# newday_alt_v0001.net
KiCad netlist of a schematic drawn in EAGLE
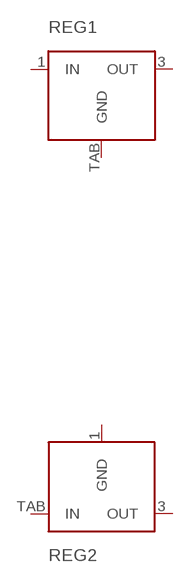
[diagram p0: schematic, sheet 1]
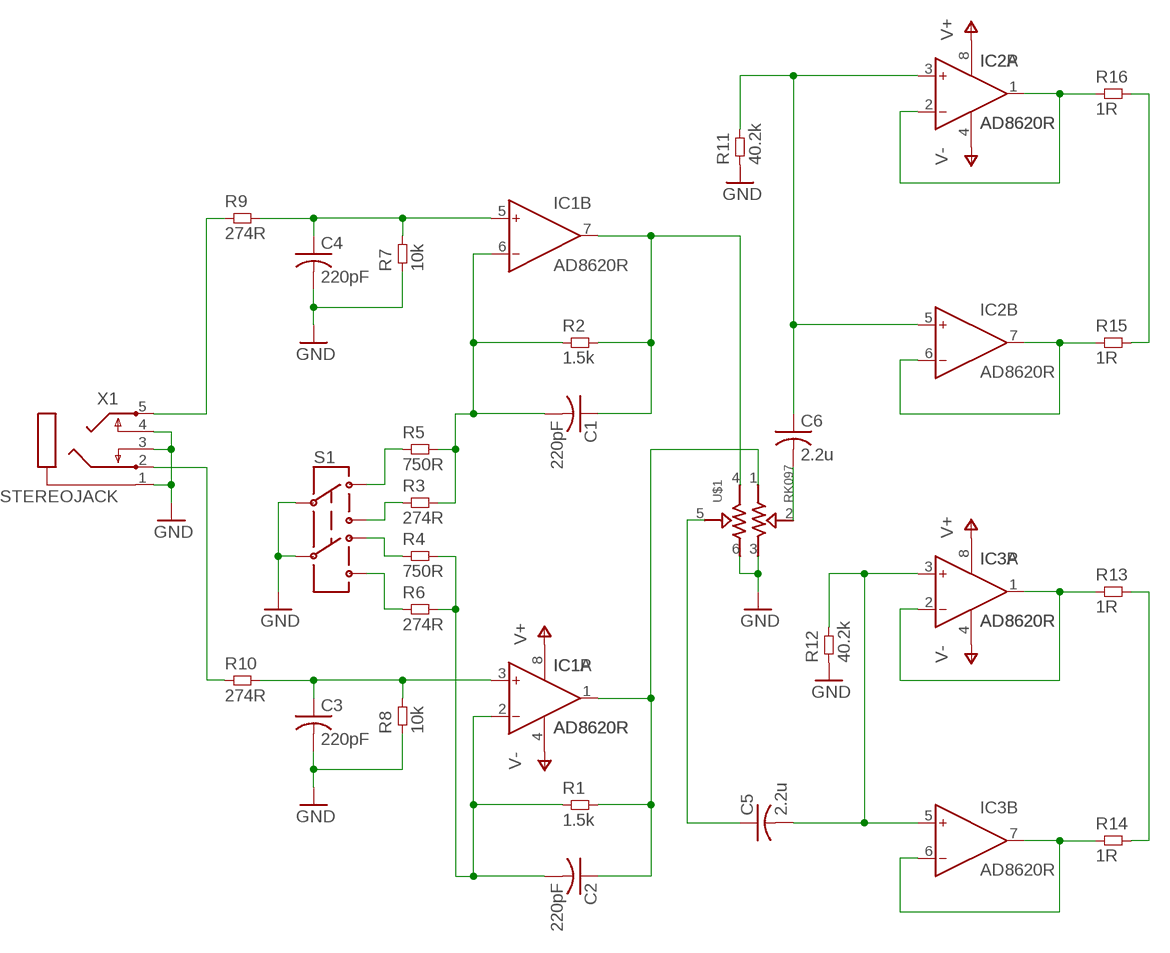
[diagram p1: schematic, sheet 2]

(export (version "E")
  (design (tool "Eeschema 10.0.6"))
  (components
    (comp (ref "REG1")
      (value "MC7812")
      (footprint "eagle-import:D2PAK")
      (libsource (lib "eagle-import") (part "MC7812"))
    )
    (comp (ref "REG2")
      (value "MC7912")
      (footprint "eagle-import:D2PAK")
      (libsource (lib "eagle-import") (part "MC7912"))
    )
    (comp (ref "C1")
      (value "220pF")
      (footprint "eagle-import:C025-040X050")
      (libsource (lib "eagle-import") (part "C-US025-040X050"))
    )
    (comp (ref "C2")
      (value "220pF")
      (footprint "eagle-import:C025-040X050")
      (libsource (lib "eagle-import") (part "C-US025-040X050"))
    )
    (comp (ref "C3")
      (value "220pF")
      (footprint "eagle-import:C025-040X050")
      (libsource (lib "eagle-import") (part "C-US025-040X050"))
    )
    (comp (ref "C4")
      (value "220pF")
      (footprint "eagle-import:C025-040X050")
      (libsource (lib "eagle-import") (part "C-US025-040X050"))
    )
    (comp (ref "C5")
      (value "2.2u")
      (footprint "eagle-import:C050-075X075")
      (libsource (lib "eagle-import") (part "C-US050-075X075"))
    )
    (comp (ref "C6")
      (value "2.2u")
      (footprint "eagle-import:C050-075X075")
      (libsource (lib "eagle-import") (part "C-US050-075X075"))
    )
    (comp (ref "IC1")
      (value "AD8620R")
      (footprint "eagle-import:SO8")
      (fields (field (name "MF") "ALTERA CORPORATION") (field (name "MPN") "AD8620ARZ"))
      (libsource (lib "eagle-import") (part "AD8620R"))
    )
    (comp (ref "IC2")
      (value "AD8620R")
      (footprint "eagle-import:SO8")
      (fields (field (name "MF") "ALTERA CORPORATION") (field (name "MPN") "AD8620ARZ"))
      (libsource (lib "eagle-import") (part "AD8620R"))
    )
    (comp (ref "IC3")
      (value "AD8620R")
      (footprint "eagle-import:SO8")
      (fields (field (name "MF") "ALTERA CORPORATION") (field (name "MPN") "AD8620ARZ"))
      (libsource (lib "eagle-import") (part "AD8620R"))
    )
    (comp (ref "R1")
      (value "1.5k")
      (footprint "eagle-import:0603L3")
      (libsource (lib "eagle-import") (part "RES0603L3"))
    )
    (comp (ref "R2")
      (value "1.5k")
      (footprint "eagle-import:0603L3")
      (libsource (lib "eagle-import") (part "RES0603L3"))
    )
    (comp (ref "R3")
      (value "274R")
      (footprint "eagle-import:0603L3")
      (libsource (lib "eagle-import") (part "RES0603L3"))
    )
    (comp (ref "R4")
      (value "750R")
      (footprint "eagle-import:0603L3")
      (libsource (lib "eagle-import") (part "RES0603L3"))
    )
    (comp (ref "R5")
      (value "750R")
      (footprint "eagle-import:0603L3")
      (libsource (lib "eagle-import") (part "RES0603L3"))
    )
    (comp (ref "R6")
      (value "274R")
      (footprint "eagle-import:0603L3")
      (libsource (lib "eagle-import") (part "RES0603L3"))
    )
    (comp (ref "R7")
      (value "10k")
      (footprint "eagle-import:0603L3")
      (libsource (lib "eagle-import") (part "RES0603L3"))
    )
    (comp (ref "R8")
      (value "10k")
      (footprint "eagle-import:0603L3")
      (libsource (lib "eagle-import") (part "RES0603L3"))
    )
    (comp (ref "R9")
      (value "274R")
      (footprint "eagle-import:0603L3")
      (libsource (lib "eagle-import") (part "RES0603L3"))
    )
    (comp (ref "R10")
      (value "274R")
      (footprint "eagle-import:0603L3")
      (libsource (lib "eagle-import") (part "RES0603L3"))
    )
    (comp (ref "R11")
      (value "40.2k")
      (footprint "eagle-import:0603L3")
      (libsource (lib "eagle-import") (part "RES0603L3"))
    )
    (comp (ref "R12")
      (value "40.2k")
      (footprint "eagle-import:0603L3")
      (libsource (lib "eagle-import") (part "RES0603L3"))
    )
    (comp (ref "R13")
      (value "1R")
      (footprint "eagle-import:1210L3")
      (libsource (lib "eagle-import") (part "RES1210L3"))
    )
    (comp (ref "R14")
      (value "1R")
      (footprint "eagle-import:1210L3")
      (libsource (lib "eagle-import") (part "RES1210L3"))
    )
    (comp (ref "R15")
      (value "1R")
      (footprint "eagle-import:1210L3")
      (libsource (lib "eagle-import") (part "RES1210L3"))
    )
    (comp (ref "R16")
      (value "1R")
      (footprint "eagle-import:1210L3")
      (libsource (lib "eagle-import") (part "RES1210L3"))
    )
    (comp (ref "S1")
      (value "SWITCH-DPDTOS")
      (footprint "eagle-import:OS")
      (libsource (lib "eagle-import") (part "SWITCH-DPDTOS"))
    )
    (comp (ref "U$1")
      (value "RK097")
      (footprint "eagle-import:RK097")
      (libsource (lib "eagle-import") (part "RK097"))
    )
    (comp (ref "X1")
      (value "STEREOJACK")
      (footprint "eagle-import:STX3100")
      (libsource (lib "eagle-import") (part "STEREOJACK"))
    )
  )
  (nets
    (net (code "1") (name "GND") (class "Default")
      (node (ref "C3") (pin "2") (pinfunction "2_2") (pintype "passive"))
      (node (ref "C4") (pin "2") (pinfunction "2_2") (pintype "passive"))
      (node (ref "R11") (pin "P$1") (pinfunction "1_P$1") (pintype "bidirectional"))
      (node (ref "R12") (pin "P$1") (pinfunction "1_P$1") (pintype "bidirectional"))
      (node (ref "R7") (pin "P$1") (pinfunction "1_P$1") (pintype "bidirectional"))
      (node (ref "R8") (pin "P$1") (pinfunction "1_P$1") (pintype "bidirectional"))
      (node (ref "S1") (pin "2") (pinfunction "2_2") (pintype "bidirectional"))
      (node (ref "S1") (pin "5") (pinfunction "5_5") (pintype "bidirectional"))
      (node (ref "U$1") (pin "3") (pinfunction "3_3") (pintype "bidirectional"))
      (node (ref "U$1") (pin "6") (pinfunction "6_6") (pintype "bidirectional"))
      (node (ref "X1") (pin "1") (pinfunction "1_1") (pintype "passive"))
      (node (ref "X1") (pin "3") (pinfunction "3_3") (pintype "passive"))
      (node (ref "X1") (pin "4") (pinfunction "4_4") (pintype "passive"))
    )
    (net (code "2") (name "Net-(C5-Pad1)") (class "Default")
      (node (ref "C5") (pin "1") (pinfunction "1_1") (pintype "passive"))
      (node (ref "U$1") (pin "5") (pinfunction "5_5") (pintype "bidirectional"))
    )
    (net (code "3") (name "Net-(C6-Pad2)") (class "Default")
      (node (ref "C6") (pin "2") (pinfunction "2_2") (pintype "passive"))
      (node (ref "U$1") (pin "2") (pinfunction "2_2") (pintype "bidirectional"))
    )
    (net (code "4") (name "Net-(IC1A-IN+)") (class "Default")
      (node (ref "C3") (pin "1") (pinfunction "1_1") (pintype "passive"))
      (node (ref "IC1") (pin "3") (pinfunction "IN+_3") (pintype "input"))
      (node (ref "R10") (pin "P$2") (pinfunction "2_P$2") (pintype "bidirectional"))
      (node (ref "R8") (pin "P$2") (pinfunction "2_P$2") (pintype "bidirectional"))
    )
    (net (code "5") (name "Net-(IC1A-IN-)") (class "Default")
      (node (ref "C2") (pin "2") (pinfunction "2_2") (pintype "passive"))
      (node (ref "IC1") (pin "2") (pinfunction "IN-_2") (pintype "input"))
      (node (ref "R1") (pin "P$1") (pinfunction "1_P$1") (pintype "bidirectional"))
      (node (ref "R4") (pin "P$2") (pinfunction "2_P$2") (pintype "bidirectional"))
      (node (ref "R6") (pin "P$2") (pinfunction "2_P$2") (pintype "bidirectional"))
    )
    (net (code "6") (name "Net-(IC1A-OUT)") (class "Default")
      (node (ref "C2") (pin "1") (pinfunction "1_1") (pintype "passive"))
      (node (ref "IC1") (pin "1") (pinfunction "OUT_1") (pintype "output"))
      (node (ref "R1") (pin "P$2") (pinfunction "2_P$2") (pintype "bidirectional"))
      (node (ref "U$1") (pin "1") (pinfunction "1_1") (pintype "bidirectional"))
    )
    (net (code "7") (name "Net-(IC1B-IN+)") (class "Default")
      (node (ref "C4") (pin "1") (pinfunction "1_1") (pintype "passive"))
      (node (ref "IC1") (pin "5") (pinfunction "IN+_5") (pintype "input"))
      (node (ref "R7") (pin "P$2") (pinfunction "2_P$2") (pintype "bidirectional"))
      (node (ref "R9") (pin "P$2") (pinfunction "2_P$2") (pintype "bidirectional"))
    )
    (net (code "8") (name "Net-(IC1B-IN-)") (class "Default")
      (node (ref "C1") (pin "2") (pinfunction "2_2") (pintype "passive"))
      (node (ref "IC1") (pin "6") (pinfunction "IN-_6") (pintype "input"))
      (node (ref "R2") (pin "P$1") (pinfunction "1_P$1") (pintype "bidirectional"))
      (node (ref "R3") (pin "P$2") (pinfunction "2_P$2") (pintype "bidirectional"))
      (node (ref "R5") (pin "P$2") (pinfunction "2_P$2") (pintype "bidirectional"))
    )
    (net (code "9") (name "Net-(IC1B-OUT)") (class "Default")
      (node (ref "C1") (pin "1") (pinfunction "1_1") (pintype "passive"))
      (node (ref "IC1") (pin "7") (pinfunction "OUT_7") (pintype "output"))
      (node (ref "R2") (pin "P$2") (pinfunction "2_P$2") (pintype "bidirectional"))
      (node (ref "U$1") (pin "4") (pinfunction "4_4") (pintype "bidirectional"))
    )
    (net (code "10") (name "Net-(IC2A-IN+)") (class "Default")
      (node (ref "C6") (pin "1") (pinfunction "1_1") (pintype "passive"))
      (node (ref "IC2") (pin "3") (pinfunction "IN+_3") (pintype "input"))
      (node (ref "IC2") (pin "5") (pinfunction "IN+_5") (pintype "input"))
      (node (ref "R11") (pin "P$2") (pinfunction "2_P$2") (pintype "bidirectional"))
    )
    (net (code "11") (name "Net-(IC2A-IN-)") (class "Default")
      (node (ref "IC2") (pin "1") (pinfunction "OUT_1") (pintype "output"))
      (node (ref "IC2") (pin "2") (pinfunction "IN-_2") (pintype "input"))
      (node (ref "R16") (pin "P$1") (pinfunction "1_P$1") (pintype "bidirectional"))
    )
    (net (code "12") (name "Net-(IC2B-IN-)") (class "Default")
      (node (ref "IC2") (pin "6") (pinfunction "IN-_6") (pintype "input"))
      (node (ref "IC2") (pin "7") (pinfunction "OUT_7") (pintype "output"))
      (node (ref "R15") (pin "P$1") (pinfunction "1_P$1") (pintype "bidirectional"))
    )
    (net (code "13") (name "Net-(IC3A-IN+)") (class "Default")
      (node (ref "C5") (pin "2") (pinfunction "2_2") (pintype "passive"))
      (node (ref "IC3") (pin "3") (pinfunction "IN+_3") (pintype "input"))
      (node (ref "IC3") (pin "5") (pinfunction "IN+_5") (pintype "input"))
      (node (ref "R12") (pin "P$2") (pinfunction "2_P$2") (pintype "bidirectional"))
    )
    (net (code "14") (name "Net-(IC3A-IN-)") (class "Default")
      (node (ref "IC3") (pin "1") (pinfunction "OUT_1") (pintype "output"))
      (node (ref "IC3") (pin "2") (pinfunction "IN-_2") (pintype "input"))
      (node (ref "R13") (pin "P$1") (pinfunction "1_P$1") (pintype "bidirectional"))
    )
    (net (code "15") (name "Net-(IC3B-IN-)") (class "Default")
      (node (ref "IC3") (pin "6") (pinfunction "IN-_6") (pintype "input"))
      (node (ref "IC3") (pin "7") (pinfunction "OUT_7") (pintype "output"))
      (node (ref "R14") (pin "P$1") (pinfunction "1_P$1") (pintype "bidirectional"))
    )
    (net (code "16") (name "Net-(R3-1)") (class "Default")
      (node (ref "R3") (pin "P$1") (pinfunction "1_P$1") (pintype "bidirectional"))
      (node (ref "S1") (pin "3") (pinfunction "3_3") (pintype "bidirectional"))
    )
    (net (code "17") (name "Net-(R4-1)") (class "Default")
      (node (ref "R4") (pin "P$1") (pinfunction "1_P$1") (pintype "bidirectional"))
      (node (ref "S1") (pin "4") (pinfunction "4_4") (pintype "bidirectional"))
    )
    (net (code "18") (name "Net-(R5-1)") (class "Default")
      (node (ref "R5") (pin "P$1") (pinfunction "1_P$1") (pintype "bidirectional"))
      (node (ref "S1") (pin "1") (pinfunction "1_1") (pintype "bidirectional"))
    )
    (net (code "19") (name "Net-(R6-1)") (class "Default")
      (node (ref "R6") (pin "P$1") (pinfunction "1_P$1") (pintype "bidirectional"))
      (node (ref "S1") (pin "6") (pinfunction "6_6") (pintype "bidirectional"))
    )
    (net (code "20") (name "Net-(R9-1)") (class "Default")
      (node (ref "R9") (pin "P$1") (pinfunction "1_P$1") (pintype "bidirectional"))
      (node (ref "X1") (pin "5") (pinfunction "5_5") (pintype "passive"))
    )
    (net (code "21") (name "Net-(R10-1)") (class "Default")
      (node (ref "R10") (pin "P$1") (pinfunction "1_P$1") (pintype "bidirectional"))
      (node (ref "X1") (pin "2") (pinfunction "2_2") (pintype "passive"))
    )
    (net (code "22") (name "Net-(R13-2)") (class "Default")
      (node (ref "R13") (pin "P$2") (pinfunction "2_P$2") (pintype "bidirectional"))
      (node (ref "R14") (pin "P$2") (pinfunction "2_P$2") (pintype "bidirectional"))
    )
    (net (code "23") (name "Net-(R15-2)") (class "Default")
      (node (ref "R15") (pin "P$2") (pinfunction "2_P$2") (pintype "bidirectional"))
      (node (ref "R16") (pin "P$2") (pinfunction "2_P$2") (pintype "bidirectional"))
    )
    (net (code "24") (name "V+") (class "Default")
      (node (ref "IC1") (pin "8") (pinfunction "V+_8") (pintype "power_in"))
      (node (ref "IC2") (pin "8") (pinfunction "V+_8") (pintype "power_in"))
      (node (ref "IC3") (pin "8") (pinfunction "V+_8") (pintype "power_in"))
    )
    (net (code "25") (name "V-") (class "Default")
      (node (ref "IC1") (pin "4") (pinfunction "V-_4") (pintype "power_in"))
      (node (ref "IC2") (pin "4") (pinfunction "V-_4") (pintype "power_in"))
      (node (ref "IC3") (pin "4") (pinfunction "V-_4") (pintype "power_in"))
    )
    (net (code "26") (name "unconnected-(REG1-GND-PadTAB)") (class "Default")
      (node (ref "REG1") (pin "TAB") (pinfunction "GND_TAB") (pintype "bidirectional"))
    )
    (net (code "27") (name "unconnected-(REG1-IN-Pad1)") (class "Default")
      (node (ref "REG1") (pin "1") (pinfunction "IN_1") (pintype "bidirectional"))
    )
    (net (code "28") (name "unconnected-(REG1-OUT-Pad3)") (class "Default")
      (node (ref "REG1") (pin "3") (pinfunction "OUT_3") (pintype "bidirectional"))
    )
    (net (code "29") (name "unconnected-(REG2-GND-Pad1)") (class "Default")
      (node (ref "REG2") (pin "1") (pinfunction "GND_1") (pintype "bidirectional"))
    )
    (net (code "30") (name "unconnected-(REG2-IN-PadTAB)") (class "Default")
      (node (ref "REG2") (pin "TAB") (pinfunction "IN_TAB") (pintype "bidirectional"))
    )
    (net (code "31") (name "unconnected-(REG2-OUT-Pad3)") (class "Default")
      (node (ref "REG2") (pin "3") (pinfunction "OUT_3") (pintype "bidirectional"))
    )
  )
)
